# SENSING.net
KiCad netlist of a schematic drawn in Altium Designer
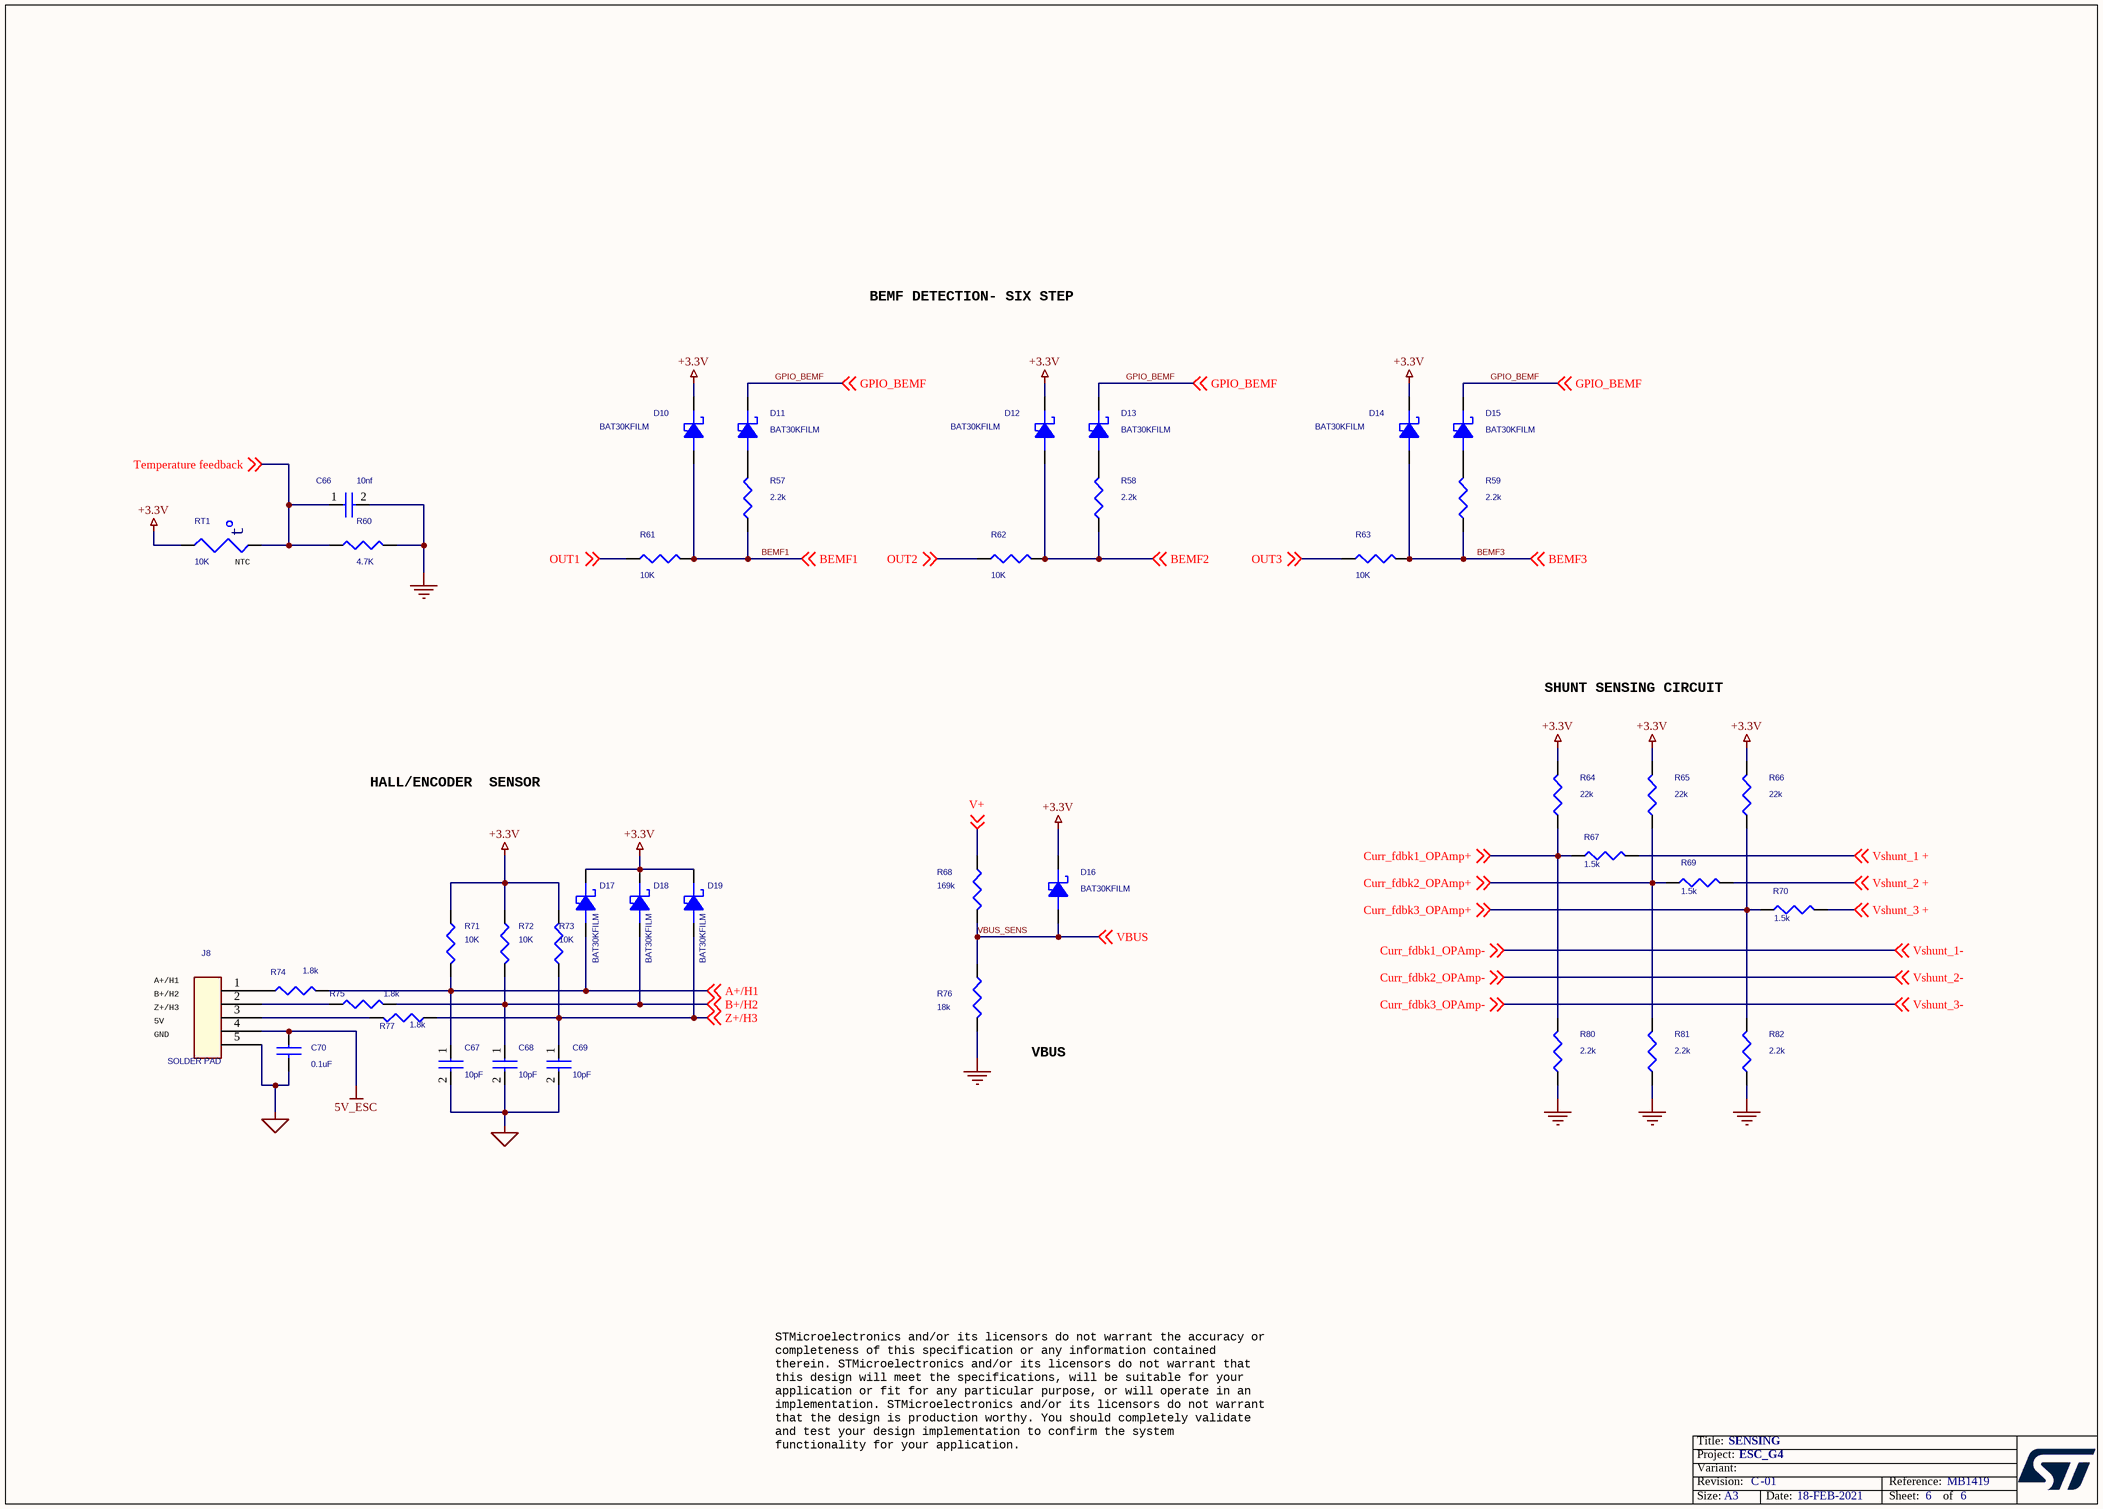
[diagram p0: SENSING.SchDoc]

(export (version "E")
  (design (tool "Eeschema 10.0.6"))
  (components
    (comp (ref "C66")
      (value "10nf")
      (footprint "C_0402")
      (description "CAP CER 10000PF 10V X7R 0402")
      (fields (field (name "PART_NUMBER") "CAP-00000003") (field (name "TOLERANCE") "10%"))
      (libsource (lib "*") (part "CAP_Dup1"))
    )
    (comp (ref "C67")
      (value "10pF")
      (footprint "C_0402")
      (description "CAP CER 10PF 10V C0G/NP0 0402")
      (fields (field (name "MANUFACTURER") "Wurth Electronics Inc.") (field (name "TOLERANCE") "5%"))
      (libsource (lib "*") (part "CAP"))
    )
    (comp (ref "C68")
      (value "10pF")
      (footprint "C_0402")
      (description "CAP CER 10PF 10V C0G/NP0 0402")
      (fields (field (name "MANUFACTURER") "Wurth Electronics Inc.") (field (name "TOLERANCE") "5%"))
      (libsource (lib "*") (part "CAP"))
    )
    (comp (ref "C69")
      (value "10pF")
      (footprint "C_0402")
      (description "CAP CER 10PF 10V C0G/NP0 0402")
      (fields (field (name "MANUFACTURER") "Wurth Electronics Inc.") (field (name "TOLERANCE") "5%"))
      (libsource (lib "*") (part "CAP"))
    )
    (comp (ref "C70")
      (value "0.1uF")
      (footprint "C_0402")
      (description "CAP CER 0.1UF 16V X7R 0402")
      (fields (field (name "MANUFACTURER") "Wurth Electronics Inc.") (field (name "TOLERANCE") "10%"))
      (libsource (lib "*") (part "CAP_4"))
    )
    (comp (ref "D10")
      (value "BAT30KFILM")
      (footprint "sodfl160x80x65l30x30n")
      (description "DIODE SCHOTTKY 30V 300MA SOD523")
      (fields (field (name "MANUFACTURER") "STMicroelectronics") (field (name "PART_NUMBER") "TMP-46"))
      (libsource (lib "*") (part "DIODE_SCHOTTKY_0"))
    )
    (comp (ref "D11")
      (value "BAT30KFILM")
      (footprint "sodfl160x80x65l30x30n")
      (description "DIODE SCHOTTKY 30V 300MA SOD523")
      (fields (field (name "PART_NUMBER") "TMP-46") (field (name "MANUFACTURER") "STMicroelectronics"))
      (libsource (lib "*") (part "DIODE_SCHOTTKY_0"))
    )
    (comp (ref "D12")
      (value "BAT30KFILM")
      (footprint "sodfl160x80x65l30x30n")
      (description "DIODE SCHOTTKY 30V 300MA SOD523")
      (fields (field (name "PART_NUMBER") "TMP-46") (field (name "MANUFACTURER") "STMicroelectronics"))
      (libsource (lib "*") (part "DIODE_SCHOTTKY_0"))
    )
    (comp (ref "D13")
      (value "BAT30KFILM")
      (footprint "sodfl160x80x65l30x30n")
      (description "DIODE SCHOTTKY 30V 300MA SOD523")
      (fields (field (name "PART_NUMBER") "TMP-46") (field (name "MANUFACTURER") "STMicroelectronics"))
      (libsource (lib "*") (part "DIODE_SCHOTTKY_0"))
    )
    (comp (ref "D14")
      (value "BAT30KFILM")
      (footprint "sodfl160x80x65l30x30n")
      (description "DIODE SCHOTTKY 30V 300MA SOD523")
      (fields (field (name "PART_NUMBER") "TMP-46") (field (name "MANUFACTURER") "STMicroelectronics"))
      (libsource (lib "*") (part "DIODE_SCHOTTKY_0"))
    )
    (comp (ref "D15")
      (value "BAT30KFILM")
      (footprint "sodfl160x80x65l30x30n")
      (description "DIODE SCHOTTKY 30V 300MA SOD523")
      (fields (field (name "PART_NUMBER") "TMP-46") (field (name "MANUFACTURER") "STMicroelectronics"))
      (libsource (lib "*") (part "DIODE_SCHOTTKY_0"))
    )
    (comp (ref "D16")
      (value "BAT30KFILM")
      (footprint "sodfl160x80x65l30x30n")
      (description "DIODE SCHOTTKY 30V 300MA SOD523")
      (fields (field (name "PART_NUMBER") "TMP-46") (field (name "MANUFACTURER") "STMicroelectronics"))
      (libsource (lib "*") (part "DIODE_SCHOTTKY_0"))
    )
    (comp (ref "D17")
      (value "BAT30KFILM")
      (footprint "sodfl160x80x65l30x30n")
      (description "DIODE SCHOTTKY 30V 300MA SOD523")
      (fields (field (name "MANUFACTURER") "STMicroelectronics") (field (name "PART_NUMBER") "TMP-46"))
      (libsource (lib "*") (part "DIODE_SCHOTTKY_0"))
    )
    (comp (ref "D18")
      (value "BAT30KFILM")
      (footprint "sodfl160x80x65l30x30n")
      (description "DIODE SCHOTTKY 30V 300MA SOD523")
      (fields (field (name "PART_NUMBER") "TMP-46") (field (name "MANUFACTURER") "STMicroelectronics"))
      (libsource (lib "*") (part "DIODE_SCHOTTKY_0"))
    )
    (comp (ref "D19")
      (value "BAT30KFILM")
      (footprint "sodfl160x80x65l30x30n")
      (description "DIODE SCHOTTKY 30V 300MA SOD523")
      (fields (field (name "MANUFACTURER") "STMicroelectronics") (field (name "PART_NUMBER") "TMP-46"))
      (libsource (lib "*") (part "DIODE_SCHOTTKY_0"))
    )
    (comp (ref "J8")
      (value "SOLDER PAD")
      (footprint "SOLDER_PAD_5PIN_SMD")
      (description "SOLDER PADS")
      (libsource (lib "*") (part "CON5"))
    )
    (comp (ref "R57")
      (value "2.2k")
      (footprint "R_0402")
      (description "RES SMD 2.2K OHM 1% 1/16W 0402")
      (fields (field (name "MANUFACTURER") "Yageo") (field (name "TOLERANCE") "1%"))
      (libsource (lib "*") (part "RES"))
    )
    (comp (ref "R58")
      (value "2.2k")
      (footprint "R_0402")
      (description "RES SMD 2.2K OHM 1% 1/16W 0402")
      (fields (field (name "MANUFACTURER") "Yageo") (field (name "TOLERANCE") "1%"))
      (libsource (lib "*") (part "RES"))
    )
    (comp (ref "R59")
      (value "2.2k")
      (footprint "R_0402")
      (description "RES SMD 2.2K OHM 1% 1/16W 0402")
      (fields (field (name "MANUFACTURER") "Yageo") (field (name "TOLERANCE") "1%"))
      (libsource (lib "*") (part "RES"))
    )
    (comp (ref "R60")
      (value "4.7K")
      (footprint "R_0402")
      (description "RES SMD 4.7K OHM 1% 1/16W 0402")
      (fields (field (name "PART_NUMBER") "TMP-403") (field (name "TOLERANCE") "1%"))
      (libsource (lib "*") (part "RES"))
    )
    (comp (ref "R61")
      (value "10K")
      (footprint "R_0603_HD")
      (description "RES SMD 10K OHM 1% 1/10W 0603")
      (fields (field (name "PART_NUMBER") "RES-00000015") (field (name "TOLERANCE") "1%"))
      (libsource (lib "*") (part "RES"))
    )
    (comp (ref "R62")
      (value "10K")
      (footprint "R_0603_HD")
      (description "RES SMD 10K OHM 1% 1/10W 0603")
      (fields (field (name "PART_NUMBER") "RES-00000015") (field (name "TOLERANCE") "1%"))
      (libsource (lib "*") (part "RES"))
    )
    (comp (ref "R63")
      (value "10K")
      (footprint "R_0603")
      (description "RES SMD 10K OHM 1% 1/10W 0603")
      (fields (field (name "PART_NUMBER") "RES-00000015") (field (name "TOLERANCE") "1%"))
      (libsource (lib "*") (part "RES"))
    )
    (comp (ref "R64")
      (value "22k")
      (footprint "r_0402")
      (description "RES SMD 22K OHM 1% 1/10W 0402")
      (fields (field (name "PART_NUMBER") "TMP-751") (field (name "TOLERANCE") "1%"))
      (libsource (lib "*") (part "RES"))
    )
    (comp (ref "R65")
      (value "22k")
      (footprint "r_0402")
      (description "RES SMD 22K OHM 1% 1/10W 0402")
      (fields (field (name "PART_NUMBER") "TMP-751") (field (name "TOLERANCE") "1%"))
      (libsource (lib "*") (part "RES"))
    )
    (comp (ref "R66")
      (value "22k")
      (footprint "r_0402")
      (description "RES SMD 22K OHM 1% 1/10W 0402")
      (fields (field (name "PART_NUMBER") "TMP-751") (field (name "TOLERANCE") "1%"))
      (libsource (lib "*") (part "RES"))
    )
    (comp (ref "R67")
      (value "1.5k")
      (footprint "R_0402")
      (description "RES SMD 1.5K OHM 1% 1/16W 0402")
      (fields (field (name "PART_NUMBER") "TMP-393") (field (name "TOLERANCE") "1%"))
      (libsource (lib "*") (part "RES"))
    )
    (comp (ref "R68")
      (value "169k")
      (footprint "R_0402")
      (description "RES SMD 169K OHM 1% 1/16W 0402")
      (fields (field (name "PART_NUMBER") "TMP-424") (field (name "TOLERANCE") "1%"))
      (libsource (lib "*") (part "RES"))
    )
    (comp (ref "R69")
      (value "1.5k")
      (footprint "R_0402")
      (description "RES SMD 1.5K OHM 1% 1/16W 0402")
      (fields (field (name "PART_NUMBER") "TMP-393") (field (name "TOLERANCE") "1%"))
      (libsource (lib "*") (part "RES"))
    )
    (comp (ref "R70")
      (value "1.5k")
      (footprint "R_0402")
      (description "RES SMD 1.5K OHM 1% 1/16W 0402")
      (fields (field (name "PART_NUMBER") "TMP-393") (field (name "TOLERANCE") "1%"))
      (libsource (lib "*") (part "RES"))
    )
    (comp (ref "R71")
      (value "10K")
      (footprint "R_0402")
      (description "RES SMD 10K OHM 1% 1/16W 0402")
      (fields (field (name "PART_NUMBER") "TMP-396") (field (name "TOLERANCE") "1%"))
      (libsource (lib "*") (part "RES"))
    )
    (comp (ref "R72")
      (value "10K")
      (footprint "R_0402")
      (description "RES SMD 10K OHM 1% 1/16W 0402")
      (fields (field (name "MANUFACTURER") "Yageo") (field (name "TOLERANCE") "1%"))
      (libsource (lib "*") (part "RES"))
    )
    (comp (ref "R73")
      (value "10K")
      (footprint "R_0402")
      (description "RES SMD 10K OHM 1% 1/16W 0402")
      (fields (field (name "MANUFACTURER") "Yageo") (field (name "TOLERANCE") "1%"))
      (libsource (lib "*") (part "RES"))
    )
    (comp (ref "R74")
      (value "1.8k")
      (footprint "R_0402")
      (description "RES SMD 1.8K OHM 1% 1/16W 0402")
      (fields (field (name "MANUFACTURER") "Yageo") (field (name "TOLERANCE") "1%"))
      (libsource (lib "*") (part "RES"))
    )
    (comp (ref "R75")
      (value "1.8k")
      (footprint "R_0402")
      (description "RES SMD 1.8K OHM 1% 1/16W 0402")
      (fields (field (name "PART_NUMBER") "TMP-394") (field (name "TOLERANCE") "1%"))
      (libsource (lib "*") (part "RES"))
    )
    (comp (ref "R76")
      (value "18k")
      (footprint "R_0402")
      (description "RES SMD 18K OHM 1% 1/16W 0402")
      (fields (field (name "PART_NUMBER") "TMP-425") (field (name "TOLERANCE") "1%"))
      (libsource (lib "*") (part "RES"))
    )
    (comp (ref "R77")
      (value "1.8k")
      (footprint "R_0402")
      (description "RES SMD 1.8K OHM 1% 1/16W 0402")
      (fields (field (name "PART_NUMBER") "TMP-394") (field (name "TOLERANCE") "1%"))
      (libsource (lib "*") (part "RES"))
    )
    (comp (ref "R80")
      (value "2.2k")
      (footprint "R_0402")
      (description "RES SMD 2.2K OHM 1% 1/16W 0402")
      (fields (field (name "PART_NUMBER") "TMP-444") (field (name "TOLERANCE") "1%"))
      (libsource (lib "*") (part "RES"))
    )
    (comp (ref "R81")
      (value "2.2k")
      (footprint "R_0402")
      (description "RES SMD 2.2K OHM 1% 1/16W 0402")
      (fields (field (name "PART_NUMBER") "TMP-444") (field (name "TOLERANCE") "1%"))
      (libsource (lib "*") (part "RES"))
    )
    (comp (ref "R82")
      (value "2.2k")
      (footprint "R_0402")
      (description "RES SMD 2.2K OHM 1% 1/16W 0402")
      (fields (field (name "PART_NUMBER") "TMP-444") (field (name "TOLERANCE") "1%"))
      (libsource (lib "*") (part "RES"))
    )
    (comp (ref "RT1")
      (value "10K")
      (footprint "R_0402")
      (description "NTC THERMISTOR 10K OHM 1% 0402")
      (fields (field (name "MANUFACTURER") "TDK Corporation") (field (name "PART_NUMBER") "TMP-423"))
      (libsource (lib "*") (part "NTC"))
    )
  )
  (nets
    (net (code "1") (name "+3.3V") (class "Default")
      (node (ref "D10") (pin "C") (pinfunction "C_C") (pintype "passive"))
      (node (ref "D12") (pin "C") (pinfunction "C_C") (pintype "passive"))
      (node (ref "D14") (pin "C") (pinfunction "C_C") (pintype "passive"))
      (node (ref "D16") (pin "C") (pinfunction "C_C") (pintype "passive"))
      (node (ref "D17") (pin "C") (pinfunction "C_C") (pintype "passive"))
      (node (ref "D18") (pin "C") (pinfunction "C_C") (pintype "passive"))
      (node (ref "D19") (pin "C") (pinfunction "C_C") (pintype "passive"))
      (node (ref "R64") (pin "2") (pinfunction "2_2") (pintype "passive"))
      (node (ref "R65") (pin "2") (pinfunction "2_2") (pintype "passive"))
      (node (ref "R66") (pin "2") (pinfunction "2_2") (pintype "passive"))
      (node (ref "R71") (pin "1") (pinfunction "1_1") (pintype "passive"))
      (node (ref "R72") (pin "1") (pinfunction "1_1") (pintype "passive"))
      (node (ref "R73") (pin "2") (pinfunction "2_2") (pintype "passive"))
      (node (ref "RT1") (pin "1") (pinfunction "1_1") (pintype "passive"))
    )
    (net (code "2") (name "5V_ESC") (class "Default")
      (node (ref "C70") (pin "1") (pinfunction "1_1") (pintype "passive"))
      (node (ref "J8") (pin "4") (pinfunction "4_4") (pintype "passive"))
    )
    (net (code "3") (name "A+{slash}H1") (class "Default")
      (node (ref "C67") (pin "1") (pinfunction "1_1") (pintype "passive"))
      (node (ref "D17") (pin "A") (pinfunction "A_A") (pintype "passive"))
      (node (ref "R71") (pin "2") (pinfunction "2_2") (pintype "passive"))
      (node (ref "R74") (pin "2") (pinfunction "2_2") (pintype "passive"))
    )
    (net (code "4") (name "B+{slash}H2") (class "Default")
      (node (ref "C68") (pin "1") (pinfunction "1_1") (pintype "passive"))
      (node (ref "D18") (pin "A") (pinfunction "A_A") (pintype "passive"))
      (node (ref "R72") (pin "2") (pinfunction "2_2") (pintype "passive"))
      (node (ref "R75") (pin "2") (pinfunction "2_2") (pintype "passive"))
    )
    (net (code "5") (name "BEMF1") (class "Default")
      (node (ref "D10") (pin "A") (pinfunction "A_A") (pintype "passive"))
      (node (ref "R57") (pin "1") (pinfunction "1_1") (pintype "passive"))
      (node (ref "R61") (pin "2") (pinfunction "2_2") (pintype "passive"))
    )
    (net (code "6") (name "BEMF2") (class "Default")
      (node (ref "D12") (pin "A") (pinfunction "A_A") (pintype "passive"))
      (node (ref "R58") (pin "1") (pinfunction "1_1") (pintype "passive"))
      (node (ref "R62") (pin "2") (pinfunction "2_2") (pintype "passive"))
    )
    (net (code "7") (name "BEMF3") (class "Default")
      (node (ref "D14") (pin "A") (pinfunction "A_A") (pintype "passive"))
      (node (ref "R59") (pin "1") (pinfunction "1_1") (pintype "passive"))
      (node (ref "R63") (pin "2") (pinfunction "2_2") (pintype "passive"))
    )
    (net (code "8") (name "Curr_fdbk1_OPAmp+") (class "Default")
      (node (ref "R64") (pin "1") (pinfunction "1_1") (pintype "passive"))
      (node (ref "R67") (pin "1") (pinfunction "1_1") (pintype "passive"))
      (node (ref "R80") (pin "2") (pinfunction "2_2") (pintype "passive"))
    )
    (net (code "10") (name "Curr_fdbk2_OPAmp+") (class "Default")
      (node (ref "R65") (pin "1") (pinfunction "1_1") (pintype "passive"))
      (node (ref "R69") (pin "1") (pinfunction "1_1") (pintype "passive"))
      (node (ref "R81") (pin "2") (pinfunction "2_2") (pintype "passive"))
    )
    (net (code "12") (name "Curr_fdbk3_OPAmp+") (class "Default")
      (node (ref "R66") (pin "1") (pinfunction "1_1") (pintype "passive"))
      (node (ref "R70") (pin "1") (pinfunction "1_1") (pintype "passive"))
      (node (ref "R82") (pin "2") (pinfunction "2_2") (pintype "passive"))
    )
    (net (code "14") (name "GND") (class "Default")
      (node (ref "C66") (pin "2") (pinfunction "2_2") (pintype "passive"))
      (node (ref "R60") (pin "2") (pinfunction "2_2") (pintype "passive"))
      (node (ref "R76") (pin "2") (pinfunction "2_2") (pintype "passive"))
      (node (ref "R80") (pin "1") (pinfunction "1_1") (pintype "passive"))
      (node (ref "R81") (pin "1") (pinfunction "1_1") (pintype "passive"))
      (node (ref "R82") (pin "1") (pinfunction "1_1") (pintype "passive"))
    )
    (net (code "15") (name "GND_SIGNAL") (class "Default")
      (node (ref "C67") (pin "2") (pinfunction "2_2") (pintype "passive"))
      (node (ref "C68") (pin "2") (pinfunction "2_2") (pintype "passive"))
      (node (ref "C69") (pin "2") (pinfunction "2_2") (pintype "passive"))
      (node (ref "C70") (pin "2") (pinfunction "2_2") (pintype "passive"))
      (node (ref "J8") (pin "5") (pinfunction "5_5") (pintype "passive"))
    )
    (net (code "16") (name "GPIO_BEMF") (class "Default")
      (node (ref "D11") (pin "C") (pinfunction "C_C") (pintype "passive"))
      (node (ref "D13") (pin "C") (pinfunction "C_C") (pintype "passive"))
      (node (ref "D15") (pin "C") (pinfunction "C_C") (pintype "passive"))
    )
    (net (code "17") (name "Net-(D11-PadA)") (class "Default")
      (node (ref "D11") (pin "A") (pinfunction "A_A") (pintype "passive"))
      (node (ref "R57") (pin "2") (pinfunction "2_2") (pintype "passive"))
    )
    (net (code "18") (name "Net-(D13-PadA)") (class "Default")
      (node (ref "D13") (pin "A") (pinfunction "A_A") (pintype "passive"))
      (node (ref "R58") (pin "2") (pinfunction "2_2") (pintype "passive"))
    )
    (net (code "19") (name "Net-(D15-PadA)") (class "Default")
      (node (ref "D15") (pin "A") (pinfunction "A_A") (pintype "passive"))
      (node (ref "R59") (pin "2") (pinfunction "2_2") (pintype "passive"))
    )
    (net (code "20") (name "Net-(J8-Pad1)") (class "Default")
      (node (ref "J8") (pin "1") (pinfunction "1_1") (pintype "passive"))
      (node (ref "R74") (pin "1") (pinfunction "1_1") (pintype "passive"))
    )
    (net (code "21") (name "Net-(J8-Pad2)") (class "Default")
      (node (ref "J8") (pin "2") (pinfunction "2_2") (pintype "passive"))
      (node (ref "R75") (pin "1") (pinfunction "1_1") (pintype "passive"))
    )
    (net (code "22") (name "Net-(J8-Pad3)") (class "Default")
      (node (ref "J8") (pin "3") (pinfunction "3_3") (pintype "passive"))
      (node (ref "R77") (pin "2") (pinfunction "2_2") (pintype "passive"))
    )
    (net (code "23") (name "OUT1") (class "Default")
      (node (ref "R61") (pin "1") (pinfunction "1_1") (pintype "passive"))
    )
    (net (code "24") (name "OUT2") (class "Default")
      (node (ref "R62") (pin "1") (pinfunction "1_1") (pintype "passive"))
    )
    (net (code "25") (name "OUT3") (class "Default")
      (node (ref "R63") (pin "1") (pinfunction "1_1") (pintype "passive"))
    )
    (net (code "26") (name "Temperature feedback") (class "Default")
      (node (ref "C66") (pin "1") (pinfunction "1_1") (pintype "passive"))
      (node (ref "R60") (pin "1") (pinfunction "1_1") (pintype "passive"))
      (node (ref "RT1") (pin "2") (pinfunction "2_2") (pintype "passive"))
    )
    (net (code "27") (name "V+") (class "Default")
      (node (ref "R68") (pin "1") (pinfunction "1_1") (pintype "passive"))
    )
    (net (code "28") (name "VBUS") (class "Default")
      (node (ref "D16") (pin "A") (pinfunction "A_A") (pintype "passive"))
      (node (ref "R68") (pin "2") (pinfunction "2_2") (pintype "passive"))
      (node (ref "R76") (pin "1") (pinfunction "1_1") (pintype "passive"))
    )
    (net (code "29") (name "Vshunt_1 +") (class "Default")
      (node (ref "R67") (pin "2") (pinfunction "2_2") (pintype "passive"))
    )
    (net (code "30") (name "Vshunt_2 +") (class "Default")
      (node (ref "R69") (pin "2") (pinfunction "2_2") (pintype "passive"))
    )
    (net (code "31") (name "Vshunt_3 +") (class "Default")
      (node (ref "R70") (pin "2") (pinfunction "2_2") (pintype "passive"))
    )
    (net (code "32") (name "Z+{slash}H3") (class "Default")
      (node (ref "C69") (pin "1") (pinfunction "1_1") (pintype "passive"))
      (node (ref "D19") (pin "A") (pinfunction "A_A") (pintype "passive"))
      (node (ref "R73") (pin "1") (pinfunction "1_1") (pintype "passive"))
      (node (ref "R77") (pin "1") (pinfunction "1_1") (pintype "passive"))
    )
  )
)
